# open-jar-tester_individual_motor_pwm_dri.net
KiCad netlist of a schematic drawn in EAGLE
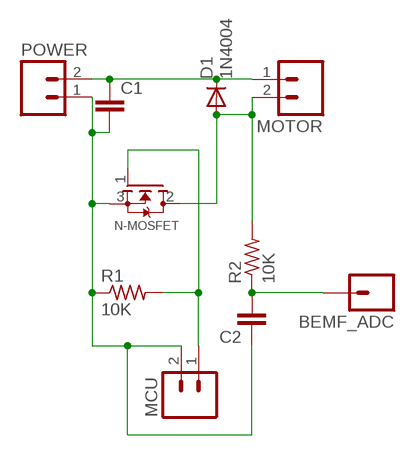
[diagram p0: schematic, sheet 1]

(export (version "E")
  (design (tool "Eeschema 10.0.6"))
  (components
    (comp (ref "BEMF_ADC")
      (value "M01PTH")
      (footprint "eagle-import:1X01")
      (libsource (lib "eagle-import") (part "M01PTH"))
    )
    (comp (ref "C1")
      (value "CAPPTH")
      (footprint "eagle-import:CAP-PTH-SMALL")
      (libsource (lib "eagle-import") (part "CAPPTH"))
    )
    (comp (ref "C2")
      (value "CAPPTH")
      (footprint "eagle-import:CAP-PTH-SMALL")
      (libsource (lib "eagle-import") (part "CAPPTH"))
    )
    (comp (ref "D1")
      (value "1N4004")
      (footprint "eagle-import:DO41-10")
      (libsource (lib "eagle-import") (part "1N4004"))
    )
    (comp (ref "MCU")
      (value "M02PTH")
      (footprint "eagle-import:1X02")
      (libsource (lib "eagle-import") (part "M02PTH"))
    )
    (comp (ref "MOTOR")
      (value "M02PTH")
      (footprint "eagle-import:1X02")
      (libsource (lib "eagle-import") (part "M02PTH"))
    )
    (comp (ref "N-MOSFET")
      (value "MOSFET-NGDS_TO220V")
      (footprint "eagle-import:TO220V")
      (libsource (lib "eagle-import") (part "MOSFET-NGDS_TO220V"))
    )
    (comp (ref "POWER")
      (value "M02PTH")
      (footprint "eagle-import:1X02")
      (libsource (lib "eagle-import") (part "M02PTH"))
    )
    (comp (ref "R1")
      (value "10K")
      (footprint "eagle-import:0207_10")
      (libsource (lib "eagle-import") (part "R-US_0207/10"))
    )
    (comp (ref "R2")
      (value "10K")
      (footprint "eagle-import:0207_10")
      (libsource (lib "eagle-import") (part "R-US_0207/10"))
    )
  )
  (nets
    (net (code "1") (name "Net-(BEMF_ADC-Pad1)") (class "Default")
      (node (ref "BEMF_ADC") (pin "1") (pinfunction "1_1") (pintype "passive"))
      (node (ref "C2") (pin "2") (pinfunction "2_2") (pintype "passive"))
      (node (ref "R2") (pin "1") (pinfunction "1_1") (pintype "passive"))
    )
    (net (code "2") (name "Net-(C1-Pad1)") (class "Default")
      (node (ref "C1") (pin "1") (pinfunction "1_1") (pintype "passive"))
      (node (ref "D1") (pin "C") (pinfunction "C_C") (pintype "passive"))
      (node (ref "MOTOR") (pin "1") (pinfunction "1_1") (pintype "passive"))
      (node (ref "POWER") (pin "2") (pinfunction "2_2") (pintype "passive"))
    )
    (net (code "3") (name "Net-(N-MOSFET-D)") (class "Default")
      (node (ref "D1") (pin "A") (pinfunction "A_A") (pintype "passive"))
      (node (ref "MOTOR") (pin "2") (pinfunction "2_2") (pintype "passive"))
      (node (ref "N-MOSFET") (pin "2") (pinfunction "D_2") (pintype "bidirectional"))
      (node (ref "R2") (pin "2") (pinfunction "2_2") (pintype "passive"))
    )
    (net (code "4") (name "Net-(N-MOSFET-G)") (class "Default")
      (node (ref "MCU") (pin "1") (pinfunction "1_1") (pintype "passive"))
      (node (ref "N-MOSFET") (pin "1") (pinfunction "G_1") (pintype "bidirectional"))
      (node (ref "R1") (pin "2") (pinfunction "2_2") (pintype "passive"))
    )
    (net (code "5") (name "Net-(N-MOSFET-S)") (class "Default")
      (node (ref "C1") (pin "2") (pinfunction "2_2") (pintype "passive"))
      (node (ref "C2") (pin "1") (pinfunction "1_1") (pintype "passive"))
      (node (ref "MCU") (pin "2") (pinfunction "2_2") (pintype "passive"))
      (node (ref "N-MOSFET") (pin "3") (pinfunction "S_3") (pintype "bidirectional"))
      (node (ref "POWER") (pin "1") (pinfunction "1_1") (pintype "passive"))
      (node (ref "R1") (pin "1") (pinfunction "1_1") (pintype "passive"))
    )
  )
)
